# nomad.net
KiCad netlist of a schematic drawn in EAGLE
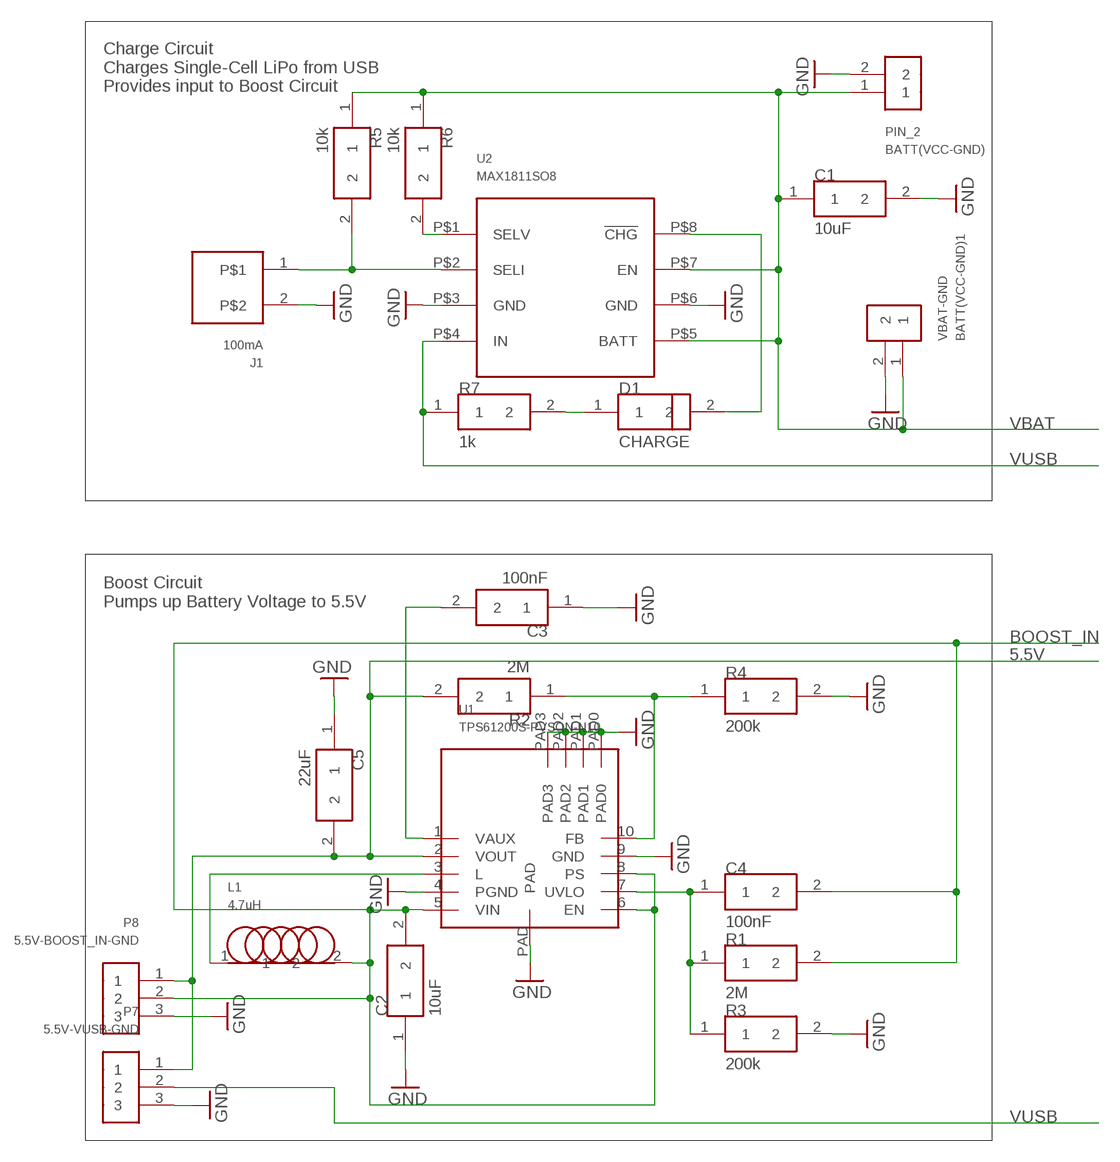
[diagram p0: schematic, sheet 1]

(export (version "E")
  (design (tool "Eeschema 10.0.6"))
  (components
    (comp (ref "BATT(VCC-GND)")
      (value "PIN_2")
      (footprint "eagle-import:PIN_2")
      (libsource (lib "eagle-import") (part "PIN_2"))
    )
    (comp (ref "BATT(VCC-GND)1")
      (value "VBAT-GND")
      (footprint "eagle-import:PIN_2")
      (libsource (lib "eagle-import") (part "PIN_2"))
    )
    (comp (ref "C1")
      (value "10uF")
      (footprint "eagle-import:0805")
      (libsource (lib "eagle-import") (part "CAP0805"))
    )
    (comp (ref "C2")
      (value "10uF")
      (footprint "eagle-import:0805")
      (libsource (lib "eagle-import") (part "CAP0805"))
    )
    (comp (ref "C3")
      (value "100nF")
      (footprint "eagle-import:0805")
      (libsource (lib "eagle-import") (part "CAP0805"))
    )
    (comp (ref "C4")
      (value "100nF")
      (footprint "eagle-import:0805")
      (libsource (lib "eagle-import") (part "CAP0805"))
    )
    (comp (ref "C5")
      (value "22uF")
      (footprint "eagle-import:1206")
      (libsource (lib "eagle-import") (part "CAP1206"))
    )
    (comp (ref "D1")
      (value "CHARGE")
      (footprint "eagle-import:0805")
      (libsource (lib "eagle-import") (part "LED0805"))
    )
    (comp (ref "J1")
      (value "100mA")
      (footprint "eagle-import:SMD_JMP")
      (libsource (lib "eagle-import") (part "JMPSMD"))
    )
    (comp (ref "L1")
      (value "4.7uH")
      (footprint "eagle-import:IND-SMD-3232")
      (libsource (lib "eagle-import") (part "INDSMD-3232"))
    )
    (comp (ref "P7")
      (value "5.5V-VUSB-GND")
      (footprint "eagle-import:PIN_3")
      (libsource (lib "eagle-import") (part "PIN_3"))
    )
    (comp (ref "P8")
      (value "5.5V-BOOST_IN-GND")
      (footprint "eagle-import:PIN_3")
      (libsource (lib "eagle-import") (part "PIN_3"))
    )
    (comp (ref "R1")
      (value "2M")
      (footprint "eagle-import:0805")
      (libsource (lib "eagle-import") (part "RES0805"))
    )
    (comp (ref "R2")
      (value "2M")
      (footprint "eagle-import:0805")
      (libsource (lib "eagle-import") (part "RES0805"))
    )
    (comp (ref "R3")
      (value "200k")
      (footprint "eagle-import:0805")
      (libsource (lib "eagle-import") (part "RES0805"))
    )
    (comp (ref "R4")
      (value "200k")
      (footprint "eagle-import:0805")
      (libsource (lib "eagle-import") (part "RES0805"))
    )
    (comp (ref "R5")
      (value "10k")
      (footprint "eagle-import:0805")
      (libsource (lib "eagle-import") (part "RES0805"))
    )
    (comp (ref "R6")
      (value "10k")
      (footprint "eagle-import:0805")
      (libsource (lib "eagle-import") (part "RES0805"))
    )
    (comp (ref "R7")
      (value "1k")
      (footprint "eagle-import:0805")
      (libsource (lib "eagle-import") (part "RES0805"))
    )
    (comp (ref "U1")
      (value "TPS61200S-PVSON-N10")
      (footprint "eagle-import:S-PVSON-N10")
      (libsource (lib "eagle-import") (part "TPS61200S-PVSON-N10"))
    )
    (comp (ref "U2")
      (value "MAX1811SO8")
      (footprint "eagle-import:SO8")
      (libsource (lib "eagle-import") (part "MAX1811SO8"))
    )
  )
  (nets
    (net (code "1") (name "/5.5V") (class "Default")
      (node (ref "C5") (pin "2") (pinfunction "2_2") (pintype "bidirectional"))
      (node (ref "P7") (pin "1") (pinfunction "1_1") (pintype "bidirectional"))
      (node (ref "P8") (pin "1") (pinfunction "1_1") (pintype "bidirectional"))
      (node (ref "R2") (pin "2") (pinfunction "2_2") (pintype "bidirectional"))
      (node (ref "U1") (pin "2") (pinfunction "VOUT_2") (pintype "bidirectional"))
    )
    (net (code "2") (name "/BOOST_IN") (class "Default")
      (node (ref "C2") (pin "2") (pinfunction "2_2") (pintype "bidirectional"))
      (node (ref "C4") (pin "2") (pinfunction "2_2") (pintype "bidirectional"))
      (node (ref "L1") (pin "2") (pinfunction "2_2") (pintype "bidirectional"))
      (node (ref "P8") (pin "2") (pinfunction "2_2") (pintype "bidirectional"))
      (node (ref "R1") (pin "2") (pinfunction "2_2") (pintype "bidirectional"))
      (node (ref "U1") (pin "5") (pinfunction "VIN_5") (pintype "bidirectional"))
      (node (ref "U1") (pin "6") (pinfunction "EN_6") (pintype "bidirectional"))
      (node (ref "U1") (pin "8") (pinfunction "PS_8") (pintype "bidirectional"))
    )
    (net (code "3") (name "/VBAT") (class "Default")
      (node (ref "BATT(VCC-GND)") (pin "1") (pinfunction "1_1") (pintype "bidirectional"))
      (node (ref "BATT(VCC-GND)1") (pin "1") (pinfunction "1_1") (pintype "bidirectional"))
      (node (ref "C1") (pin "1") (pinfunction "1_1") (pintype "bidirectional"))
      (node (ref "R5") (pin "1") (pinfunction "1_1") (pintype "bidirectional"))
      (node (ref "R6") (pin "1") (pinfunction "1_1") (pintype "bidirectional"))
      (node (ref "U2") (pin "P$5") (pinfunction "BATT_P$5") (pintype "bidirectional"))
      (node (ref "U2") (pin "P$7") (pinfunction "EN_P$7") (pintype "bidirectional"))
    )
    (net (code "4") (name "/VUSB") (class "Default")
      (node (ref "P7") (pin "2") (pinfunction "2_2") (pintype "bidirectional"))
      (node (ref "R7") (pin "1") (pinfunction "1_1") (pintype "bidirectional"))
      (node (ref "U2") (pin "P$4") (pinfunction "IN_P$4") (pintype "bidirectional"))
    )
    (net (code "5") (name "GND") (class "Default")
      (node (ref "BATT(VCC-GND)") (pin "2") (pinfunction "2_2") (pintype "bidirectional"))
      (node (ref "BATT(VCC-GND)1") (pin "2") (pinfunction "2_2") (pintype "bidirectional"))
      (node (ref "C1") (pin "2") (pinfunction "2_2") (pintype "bidirectional"))
      (node (ref "C2") (pin "1") (pinfunction "1_1") (pintype "bidirectional"))
      (node (ref "C3") (pin "1") (pinfunction "1_1") (pintype "bidirectional"))
      (node (ref "C5") (pin "1") (pinfunction "1_1") (pintype "bidirectional"))
      (node (ref "J1") (pin "2") (pinfunction "P$2_2") (pintype "bidirectional"))
      (node (ref "P7") (pin "3") (pinfunction "3_3") (pintype "bidirectional"))
      (node (ref "P8") (pin "3") (pinfunction "3_3") (pintype "bidirectional"))
      (node (ref "R3") (pin "2") (pinfunction "2_2") (pintype "bidirectional"))
      (node (ref "R4") (pin "2") (pinfunction "2_2") (pintype "bidirectional"))
      (node (ref "U1") (pin "4") (pinfunction "PGND_4") (pintype "bidirectional"))
      (node (ref "U1") (pin "9") (pinfunction "GND_9") (pintype "bidirectional"))
      (node (ref "U1") (pin "PAD") (pinfunction "PAD_PAD") (pintype "bidirectional"))
      (node (ref "U1") (pin "PAD0") (pinfunction "PAD0_PAD0") (pintype "bidirectional"))
      (node (ref "U1") (pin "PAD1") (pinfunction "PAD1_PAD1") (pintype "bidirectional"))
      (node (ref "U1") (pin "PAD2") (pinfunction "PAD2_PAD2") (pintype "bidirectional"))
      (node (ref "U1") (pin "PAD3") (pinfunction "PAD3_PAD3") (pintype "bidirectional"))
      (node (ref "U2") (pin "P$3") (pinfunction "GND_P$3") (pintype "bidirectional"))
      (node (ref "U2") (pin "P$6") (pinfunction "GND_P$6") (pintype "bidirectional"))
    )
    (net (code "6") (name "Net-(D1-Pad1)") (class "Default")
      (node (ref "D1") (pin "1") (pinfunction "1_1") (pintype "bidirectional"))
      (node (ref "R7") (pin "2") (pinfunction "2_2") (pintype "bidirectional"))
    )
    (net (code "7") (name "Net-(J1-P$1)") (class "Default")
      (node (ref "J1") (pin "1") (pinfunction "P$1_1") (pintype "bidirectional"))
      (node (ref "R5") (pin "2") (pinfunction "2_2") (pintype "bidirectional"))
      (node (ref "U2") (pin "P$2") (pinfunction "SELI_P$2") (pintype "bidirectional"))
    )
    (net (code "8") (name "Net-(U1-FB)") (class "Default")
      (node (ref "R2") (pin "1") (pinfunction "1_1") (pintype "bidirectional"))
      (node (ref "R4") (pin "1") (pinfunction "1_1") (pintype "bidirectional"))
      (node (ref "U1") (pin "10") (pinfunction "FB_10") (pintype "bidirectional"))
    )
    (net (code "9") (name "Net-(U1-L)") (class "Default")
      (node (ref "L1") (pin "1") (pinfunction "1_1") (pintype "bidirectional"))
      (node (ref "U1") (pin "3") (pinfunction "L_3") (pintype "bidirectional"))
    )
    (net (code "10") (name "Net-(U1-UVLO)") (class "Default")
      (node (ref "C4") (pin "1") (pinfunction "1_1") (pintype "bidirectional"))
      (node (ref "R1") (pin "1") (pinfunction "1_1") (pintype "bidirectional"))
      (node (ref "R3") (pin "1") (pinfunction "1_1") (pintype "bidirectional"))
      (node (ref "U1") (pin "7") (pinfunction "UVLO_7") (pintype "bidirectional"))
    )
    (net (code "11") (name "Net-(U1-VAUX)") (class "Default")
      (node (ref "C3") (pin "2") (pinfunction "2_2") (pintype "bidirectional"))
      (node (ref "U1") (pin "1") (pinfunction "VAUX_1") (pintype "bidirectional"))
    )
    (net (code "12") (name "Net-(U2-SELV)") (class "Default")
      (node (ref "R6") (pin "2") (pinfunction "2_2") (pintype "bidirectional"))
      (node (ref "U2") (pin "P$1") (pinfunction "SELV_P$1") (pintype "bidirectional"))
    )
    (net (code "13") (name "Net-(U2-~{CHG})") (class "Default")
      (node (ref "D1") (pin "2") (pinfunction "2_2") (pintype "bidirectional"))
      (node (ref "U2") (pin "P$8") (pinfunction "~{CHG}_P$8") (pintype "bidirectional"))
    )
  )
)
